# PROGRAM.net
KiCad netlist of a schematic drawn in Altium Designer
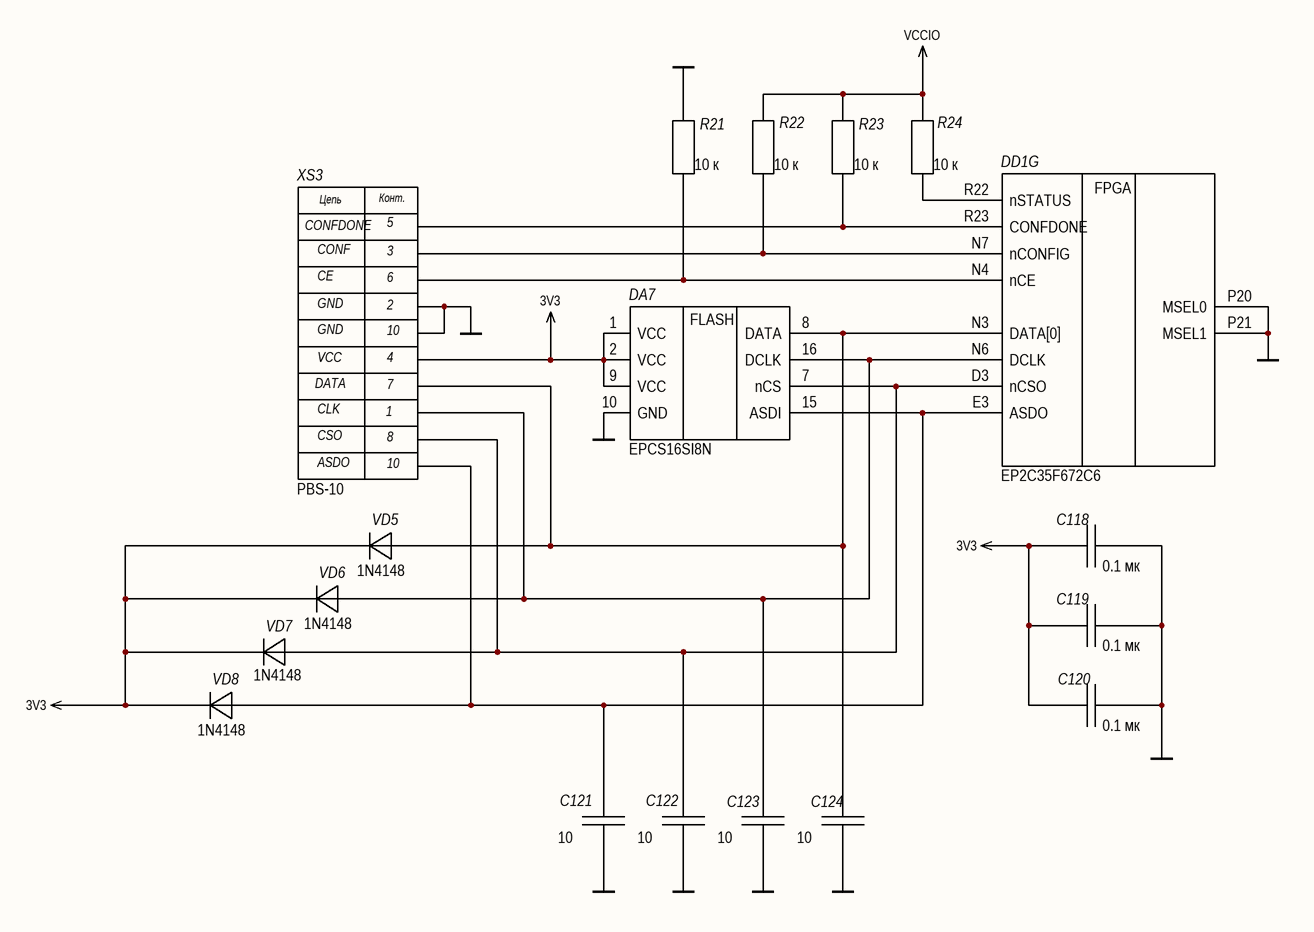
[diagram p0: PROGRAM.SchDoc]

(export (version "E")
  (design (tool "Eeschema 10.0.6"))
  (components
    (comp (ref "C118") (value "~") (libsource (lib "Schlib1") (part "C")))
    (comp (ref "C119") (value "~") (libsource (lib "Schlib1") (part "C")))
    (comp (ref "C120") (value "~") (libsource (lib "Schlib1") (part "C")))
    (comp (ref "C121") (value "~") (libsource (lib "Schlib1") (part "C")))
    (comp (ref "C122") (value "~") (libsource (lib "Schlib1") (part "C")))
    (comp (ref "C123") (value "~") (libsource (lib "Schlib1") (part "C")))
    (comp (ref "C124") (value "~") (libsource (lib "Schlib1") (part "C")))
    (comp (ref "DA7") (value "EPCS16SI8N") (libsource (lib "Schlib1") (part "EPCS16")))
    (comp (ref "DD1") (value "EP2C35F672C6") (libsource (lib "Schlib1") (part "PLIS")))
    (comp (ref "R21") (value "~") (libsource (lib "Schlib1") (part "R")))
    (comp (ref "R22") (value "~") (libsource (lib "Schlib1") (part "R")))
    (comp (ref "R23") (value "~") (libsource (lib "Schlib1") (part "R")))
    (comp (ref "R24") (value "~") (libsource (lib "Schlib1") (part "R")))
    (comp (ref "VD5")
      (value "*")
      (fields (field (name "VALUEMANUFACTURERPARTNUMBER") "BAT54HT1G"))
      (libsource (lib "Schlib1") (part "diode"))
    )
    (comp (ref "VD6")
      (value "*")
      (fields (field (name "VALUEMANUFACTURERPARTNUMBER") "BAT54HT1G"))
      (libsource (lib "Schlib1") (part "diode"))
    )
    (comp (ref "VD7")
      (value "*")
      (fields (field (name "VALUEMANUFACTURERPARTNUMBER") "BAT54HT1G"))
      (libsource (lib "Schlib1") (part "diode"))
    )
    (comp (ref "VD8")
      (value "*")
      (fields (field (name "VALUEMANUFACTURERPARTNUMBER") "BAT54HT1G"))
      (libsource (lib "Schlib1") (part "diode"))
    )
    (comp (ref "XS3") (value "PBS-10") (libsource (lib "Schlib1") (part "HEADER 10PIN")))
  )
  (nets
    (net (code "1") (name "3V3") (class "Default")
      (node (ref "C118") (pin "2") (pintype "passive"))
      (node (ref "C119") (pin "2") (pintype "passive"))
      (node (ref "C120") (pin "2") (pintype "passive"))
      (node (ref "DA7") (pin "1") (pinfunction "VCC_1") (pintype "passive"))
      (node (ref "DA7") (pin "2") (pinfunction "VCC_2") (pintype "passive"))
      (node (ref "DA7") (pin "9") (pinfunction "VCC_9") (pintype "passive"))
      (node (ref "VD5") (pin "2") (pintype "passive"))
      (node (ref "VD6") (pin "2") (pintype "passive"))
      (node (ref "VD7") (pin "2") (pintype "passive"))
      (node (ref "VD8") (pin "2") (pintype "passive"))
      (node (ref "XS3") (pin "4") (pinfunction "4_4") (pintype "passive"))
    )
    (net (code "2") (name "GND") (class "Default")
      (node (ref "C118") (pin "1") (pintype "passive"))
      (node (ref "C119") (pin "1") (pintype "passive"))
      (node (ref "C120") (pin "1") (pintype "passive"))
      (node (ref "C121") (pin "1") (pintype "passive"))
      (node (ref "C122") (pin "1") (pintype "passive"))
      (node (ref "C123") (pin "1") (pintype "passive"))
      (node (ref "C124") (pin "1") (pintype "passive"))
      (node (ref "DA7") (pin "10") (pinfunction "GND_10") (pintype "passive"))
      (node (ref "DD1") (pin "P20") (pinfunction "MSEL0_P20") (pintype "passive"))
      (node (ref "DD1") (pin "P21") (pinfunction "MSEL1_P21") (pintype "passive"))
      (node (ref "R21") (pin "2") (pinfunction "2_2") (pintype "passive"))
      (node (ref "XS3") (pin "5") (pinfunction "5_5") (pintype "passive"))
      (node (ref "XS3") (pin "6") (pinfunction "6_6") (pintype "passive"))
    )
    (net (code "3") (name "Net-(DA7-ASDI)") (class "Default")
      (node (ref "C121") (pin "2") (pintype "passive"))
      (node (ref "DA7") (pin "15") (pinfunction "ASDI_15") (pintype "passive"))
      (node (ref "DD1") (pin "E3") (pinfunction "ASDO_E3") (pintype "passive"))
      (node (ref "VD8") (pin "1") (pintype "passive"))
      (node (ref "XS3") (pin "10") (pinfunction "10_10") (pintype "passive"))
    )
    (net (code "4") (name "Net-(DA7-DATA)") (class "Default")
      (node (ref "C124") (pin "2") (pintype "passive"))
      (node (ref "DA7") (pin "8") (pinfunction "DATA_8") (pintype "passive"))
      (node (ref "DD1") (pin "N3") (pinfunction "DATA[0]_N3") (pintype "passive"))
      (node (ref "VD5") (pin "1") (pintype "passive"))
      (node (ref "XS3") (pin "8") (pinfunction "8_8") (pintype "passive"))
    )
    (net (code "5") (name "Net-(DA7-DCLK)") (class "Default")
      (node (ref "C123") (pin "2") (pintype "passive"))
      (node (ref "DA7") (pin "16") (pinfunction "DCLK_16") (pintype "passive"))
      (node (ref "DD1") (pin "N6") (pinfunction "DCLK_N6") (pintype "passive"))
      (node (ref "VD6") (pin "1") (pintype "passive"))
      (node (ref "XS3") (pin "7") (pinfunction "7_7") (pintype "passive"))
    )
    (net (code "6") (name "Net-(DA7-nCS)") (class "Default")
      (node (ref "C122") (pin "2") (pintype "passive"))
      (node (ref "DA7") (pin "7") (pinfunction "nCS_7") (pintype "passive"))
      (node (ref "DD1") (pin "D3") (pinfunction "nCSO_D3") (pintype "passive"))
      (node (ref "VD7") (pin "1") (pintype "passive"))
      (node (ref "XS3") (pin "9") (pinfunction "9_9") (pintype "passive"))
    )
    (net (code "7") (name "Net-(DD1G-CONFDONE)") (class "Default")
      (node (ref "DD1") (pin "R23") (pinfunction "CONFDONE_R23") (pintype "passive"))
      (node (ref "R23") (pin "1") (pinfunction "1_1") (pintype "passive"))
      (node (ref "XS3") (pin "5") (pinfunction "CONFDONE_5") (pintype "passive"))
    )
    (net (code "8") (name "Net-(DD1G-nCE)") (class "Default")
      (node (ref "DD1") (pin "N4") (pinfunction "nCE_N4") (pintype "passive"))
      (node (ref "R21") (pin "1") (pinfunction "1_1") (pintype "passive"))
      (node (ref "XS3") (pin "3") (pinfunction "3_3") (pintype "passive"))
    )
    (net (code "9") (name "Net-(DD1G-nCONFIG)") (class "Default")
      (node (ref "DD1") (pin "N7") (pinfunction "nCONFIG_N7") (pintype "passive"))
      (node (ref "R22") (pin "1") (pinfunction "1_1") (pintype "passive"))
      (node (ref "XS3") (pin "2") (pinfunction "2_2") (pintype "passive"))
    )
    (net (code "10") (name "Net-(DD1G-nSTATUS)") (class "Default")
      (node (ref "DD1") (pin "R22") (pinfunction "nSTATUS_R22") (pintype "passive"))
      (node (ref "R24") (pin "1") (pinfunction "1_1") (pintype "passive"))
    )
    (net (code "11") (name "VCCIO") (class "Default")
      (node (ref "R22") (pin "2") (pinfunction "2_2") (pintype "passive"))
      (node (ref "R23") (pin "2") (pinfunction "2_2") (pintype "passive"))
      (node (ref "R24") (pin "2") (pinfunction "2_2") (pintype "passive"))
    )
  )
)
